# PDM_Mk21.net
KiCad netlist of a schematic drawn in Altium Designer
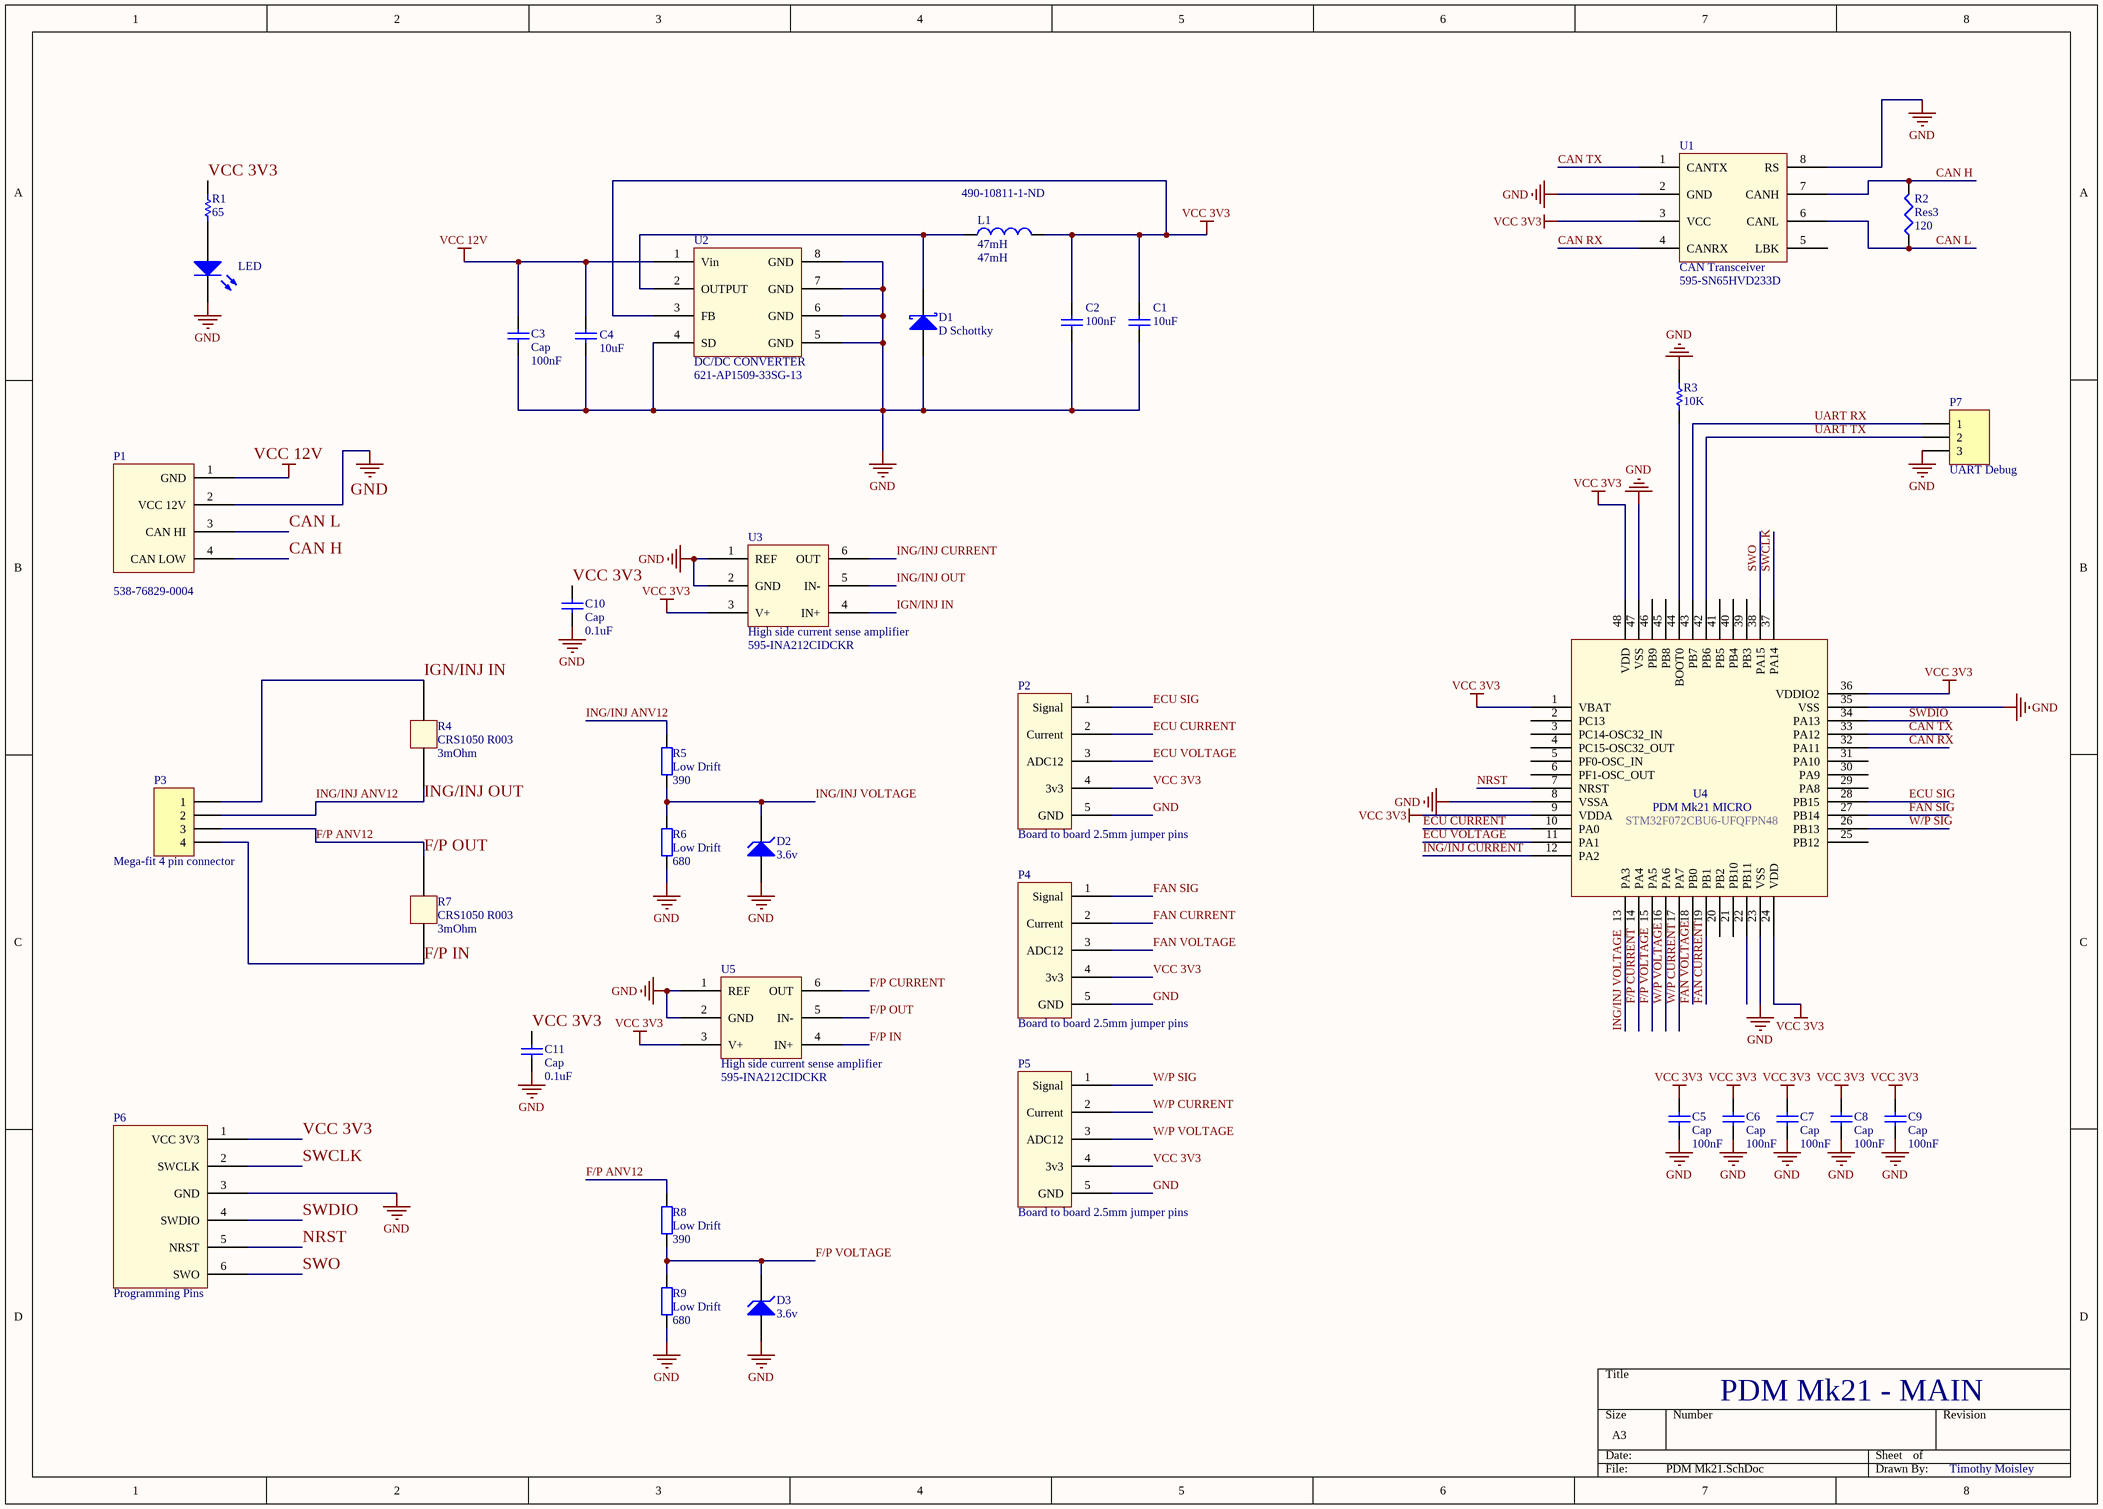
[diagram p0: PDM Mk21.SchDoc]

(export (version "E")
  (design (tool "Eeschema 10.0.6"))
  (components
    (comp (ref "C1")
      (value "10uF")
      (footprint "SMD CAPACITOR 220UF 16V")
      (description "Capacitor (Semiconductor SIM Model)")
      (fields (field (name "PUBLISHER") "Altium Limited"))
      (libsource (lib "Miscellaneous Devices") (part "Cap Semi"))
    )
    (comp (ref "C2")
      (value "100nF")
      (footprint "R0805")
      (description "Capacitor (Semiconductor SIM Model)")
      (fields (field (name "PUBLISHER") "Altium Limited"))
      (libsource (lib "Miscellaneous Devices") (part "Cap Semi"))
    )
    (comp (ref "C3")
      (value "Cap")
      (footprint "R0805")
      (description "Capacitor")
      (fields (field (name "ALTIUM_VALUE") "100nF") (field (name "PUBLISHER") "Altium Limited"))
      (libsource (lib "Miscellaneous Devices") (part "Cap"))
    )
    (comp (ref "C4")
      (value "10uF")
      (footprint "SMD CAPACITOR 220UF 16V")
      (description "Capacitor (Semiconductor SIM Model)")
      (fields (field (name "PUBLISHER") "Altium Limited"))
      (libsource (lib "Miscellaneous Devices") (part "Cap Semi"))
    )
    (comp (ref "C5")
      (value "Cap")
      (footprint "R0805")
      (description "Capacitor")
      (fields (field (name "ALTIUM_VALUE") "100nF") (field (name "PUBLISHER") "Altium Limited"))
      (libsource (lib "Miscellaneous Devices") (part "Cap"))
    )
    (comp (ref "C6")
      (value "Cap")
      (footprint "R0805")
      (description "Capacitor")
      (fields (field (name "ALTIUM_VALUE") "100nF") (field (name "PUBLISHER") "Altium Limited"))
      (libsource (lib "Miscellaneous Devices") (part "Cap"))
    )
    (comp (ref "C7")
      (value "Cap")
      (footprint "R0805")
      (description "Capacitor")
      (fields (field (name "ALTIUM_VALUE") "100nF") (field (name "PUBLISHER") "Altium Limited"))
      (libsource (lib "Miscellaneous Devices") (part "Cap"))
    )
    (comp (ref "C8")
      (value "Cap")
      (footprint "R0805")
      (description "Capacitor")
      (fields (field (name "ALTIUM_VALUE") "100nF") (field (name "PUBLISHER") "Altium Limited"))
      (libsource (lib "Miscellaneous Devices") (part "Cap"))
    )
    (comp (ref "C9")
      (value "Cap")
      (footprint "R0805")
      (description "Capacitor")
      (fields (field (name "ALTIUM_VALUE") "100nF") (field (name "PUBLISHER") "Altium Limited"))
      (libsource (lib "Miscellaneous Devices") (part "Cap"))
    )
    (comp (ref "C10")
      (value "Cap")
      (footprint "R0805")
      (description "Capacitor")
      (fields (field (name "ALTIUM_VALUE") "0.1uF") (field (name "PUBLISHER") "Altium Limited"))
      (libsource (lib "Miscellaneous Devices") (part "Cap"))
    )
    (comp (ref "C11")
      (value "Cap")
      (footprint "R0805")
      (description "Capacitor")
      (fields (field (name "ALTIUM_VALUE") "0.1uF") (field (name "PUBLISHER") "Altium Limited"))
      (libsource (lib "Miscellaneous Devices") (part "Cap"))
    )
    (comp (ref "D1")
      (value "D Schottky")
      (footprint "Diode")
      (description "Schottky Diode")
      (fields (field (name "PUBLISHER") "Altium Limited"))
      (libsource (lib "Miscellaneous Devices") (part "D Schottky"))
    )
    (comp (ref "D2")
      (value "3.6v")
      (footprint "BZX84CxxxET1G")
      (description "Zener Diode")
      (fields (field (name "PUBLISHER") "Altium Limited"))
      (libsource (lib "Miscellaneous Devices") (part "D Zener"))
    )
    (comp (ref "D3")
      (value "3.6v")
      (footprint "BZX84CxxxET1G")
      (description "Zener Diode")
      (fields (field (name "PUBLISHER") "Altium Limited"))
      (libsource (lib "Miscellaneous Devices") (part "D Zener"))
    )
    (comp (ref "L1")
      (value "47mH")
      (footprint "Inductor")
      (description "Inductor")
      (fields
        (field (name "ALTIUM_VALUE") "47mH")
        (field (name "MANUFACTURER") "Murata - TOKO")
        (field (name "MANUFACTURER PART NUMBER") "1255AY-470M=P3")
        (field (name "SUPPLIER PART NUMBER 2") "490-10811-1-ND")
        (field (name "PUBLISHER") "Altium Limited")
      )
      (libsource (lib "Miscellaneous Devices") (part "Inductor"))
    )
    (comp (ref "LED")
      (value "~")
      (footprint "LED-0")
      (description "Typical INFRARED GaAs LED")
      (fields (field (name "PUBLISHER") "Altium Limited"))
      (libsource (lib "Miscellaneous Devices") (part "LED0"))
    )
    (comp (ref "P1")
      (value "Mega-fit 4 pin connector")
      (footprint "SMD 4Wire")
      (description "MOLEX mega-fit 4 pin connector")
      (fields
        (field (name "MANUFACTURER") "MOLEX")
        (field (name "MANUFACTURER PART NO.") "76829-0004")
        (field (name "SUPPLIER PART NO.") "538-76829-0004")
      )
      (libsource (lib "PDM Mk21") (part "Mega-fit 4 pin connector"))
    )
    (comp (ref "P2")
      (value "Board to board 2.5mm jumper pins")
      (footprint "Board-Board Jumper")
      (libsource (lib "PDM Mk21") (part "Board-Board Jumper"))
    )
    (comp (ref "P3")
      (value "Mega-fit 4 pin connector")
      (footprint "Mega-fit 4 pin connector")
      (description "Header, 4-Pin")
      (fields (field (name "PUBLISHER") "Altium Limited"))
      (libsource (lib "Miscellaneous Connectors") (part "Header 4"))
    )
    (comp (ref "P4")
      (value "Board to board 2.5mm jumper pins")
      (footprint "Board-Board Jumper")
      (libsource (lib "PDM Mk21") (part "Board-Board Jumper"))
    )
    (comp (ref "P5")
      (value "Board to board 2.5mm jumper pins")
      (footprint "Board-Board Jumper")
      (libsource (lib "PDM Mk21") (part "Board-Board Jumper"))
    )
    (comp (ref "P6")
      (value "Programming Pins")
      (footprint "Programming Pins")
      (description "STM32 micro programming pins")
      (libsource (lib "PDM Mk21") (part "Programming Pins"))
    )
    (comp (ref "P7")
      (value "UART Debug")
      (footprint "HDR1X3")
      (description "Header, 3-Pin")
      (fields (field (name "PUBLISHER") "Altium Limited"))
      (libsource (lib "Miscellaneous Connectors") (part "Header 3"))
    )
    (comp (ref "R1")
      (value "65")
      (footprint "R0805")
      (description "Resistor")
      (fields (field (name "Comment") "GND") (field (name "PUBLISHER") "Altium Limited"))
      (libsource (lib "Miscellaneous Devices") (part "Res1"))
    )
    (comp (ref "R2")
      (value "Res3")
      (footprint "J1-0603")
      (description "Resistor")
      (fields (field (name "ALTIUM_VALUE") "120") (field (name "PUBLISHER") "Altium Limited"))
      (libsource (lib "Miscellaneous Devices") (part "Res3"))
    )
    (comp (ref "R3")
      (value "10K")
      (footprint "R0805")
      (description "Resistor")
      (fields (field (name "Comment") "GND") (field (name "PUBLISHER") "Altium Limited"))
      (libsource (lib "Miscellaneous Devices") (part "Res1"))
    )
    (comp (ref "R4")
      (value "CRS1050 R003")
      (footprint "CRS1050")
      (description "Current Shunt Resistor")
      (fields (field (name "ALTIUM_VALUE") "3mOhm"))
      (libsource (lib "PDM Mk21") (part "CSR1050"))
    )
    (comp (ref "R5")
      (value "Low Drift")
      (footprint "R0805")
      (description "Resistor")
      (fields (field (name "ALTIUM_VALUE") "390") (field (name "PUBLISHER") "Altium Limited"))
      (libsource (lib "Miscellaneous Devices") (part "Res2"))
    )
    (comp (ref "R6")
      (value "Low Drift")
      (footprint "R0805")
      (description "Resistor")
      (fields (field (name "ALTIUM_VALUE") "680") (field (name "PUBLISHER") "Altium Limited"))
      (libsource (lib "Miscellaneous Devices") (part "Res2"))
    )
    (comp (ref "R7")
      (value "CRS1050 R003")
      (footprint "CRS1050")
      (description "Current Shunt Resistor")
      (fields (field (name "ALTIUM_VALUE") "3mOhm"))
      (libsource (lib "") (part "CSR1050_1"))
    )
    (comp (ref "R8")
      (value "Low Drift")
      (footprint "R0805")
      (description "Resistor")
      (fields (field (name "ALTIUM_VALUE") "390") (field (name "PUBLISHER") "Altium Limited"))
      (libsource (lib "Miscellaneous Devices") (part "Res2"))
    )
    (comp (ref "R9")
      (value "Low Drift")
      (footprint "R0805")
      (description "Resistor")
      (fields (field (name "ALTIUM_VALUE") "680") (field (name "PUBLISHER") "Altium Limited"))
      (libsource (lib "Miscellaneous Devices") (part "Res2"))
    )
    (comp (ref "U1")
      (value "CAN Transceiver")
      (footprint "CAN Transceiver")
      (fields (field (name "SUPPLIER PART NO.") "595-SN65HVD233D"))
      (libsource (lib "PDM Mk21") (part "595-SN65HVD233D"))
    )
    (comp (ref "U2")
      (value "DC/DC CONVERTER")
      (footprint "DC/DC Converter")
      (fields (field (name "SUPPLIER PART NUMBER") "621-AP1509-33SG-13"))
      (libsource (lib "PDM Mk21") (part "AP1509-33SG-13"))
    )
    (comp (ref "U3")
      (value "High side current sense amplifier")
      (footprint "INA212")
      (fields
        (field (name "MANUFACTURER") "Texas Instruments")
        (field (name "MANUFACTURER PART NO.") "INA212CIDCKR")
        (field (name "SUPPLIER PART NUMBER") "595-INA212CIDCKR")
      )
      (libsource (lib "PDM Mk21") (part "INA212"))
    )
    (comp (ref "U4")
      (value "PDM Mk21 MICRO")
      (footprint "QFN50P700X700X60_HS-49N")
      (fields
        (field (name "MANUFACTURER") "ST Microelectrics")
        (field (name "PART NUMBER") "STM32F072CBU6-UFQFPN48")
      )
      (libsource (lib "PDM Mk21") (part "STM32F072CBU6"))
    )
    (comp (ref "U5")
      (value "High side current sense amplifier")
      (footprint "INA212")
      (fields
        (field (name "MANUFACTURER") "Texas Instruments")
        (field (name "MANUFACTURER PART NO.") "INA212CIDCKR")
        (field (name "SUPPLIER PART NUMBER") "595-INA212CIDCKR")
      )
      (libsource (lib "PDM Mk21") (part "INA212"))
    )
  )
  (nets
    (net (code "1") (name "/CAN H") (class "Default")
      (node (ref "P1") (pin "4") (pinfunction "CAN_LOW_4") (pintype "passive"))
      (node (ref "R2") (pin "2") (pinfunction "2_2") (pintype "passive"))
      (node (ref "U1") (pin "7") (pinfunction "CANH_7") (pintype "passive"))
    )
    (net (code "2") (name "/CAN L") (class "Default")
      (node (ref "P1") (pin "3") (pinfunction "CAN_HI_3") (pintype "passive"))
      (node (ref "R2") (pin "1") (pinfunction "1_1") (pintype "passive"))
      (node (ref "U1") (pin "6") (pinfunction "CANL_6") (pintype "passive"))
    )
    (net (code "3") (name "/CAN RX") (class "Default")
      (node (ref "U1") (pin "4") (pinfunction "CANRX_4") (pintype "passive"))
      (node (ref "U4") (pin "32") (pinfunction "PA11_32") (pintype "passive"))
    )
    (net (code "4") (name "/CAN TX") (class "Default")
      (node (ref "U1") (pin "1") (pinfunction "CANTX_1") (pintype "passive"))
      (node (ref "U4") (pin "33") (pinfunction "PA12_33") (pintype "passive"))
    )
    (net (code "5") (name "/ECU CURRENT") (class "Default")
      (node (ref "P2") (pin "2") (pinfunction "Current_2") (pintype "passive"))
      (node (ref "U4") (pin "10") (pinfunction "PA0_10") (pintype "passive"))
    )
    (net (code "6") (name "/ECU SIG") (class "Default")
      (node (ref "P2") (pin "1") (pinfunction "Signal_1") (pintype "passive"))
      (node (ref "U4") (pin "28") (pinfunction "PB15_28") (pintype "passive"))
    )
    (net (code "7") (name "/ECU VOLTAGE") (class "Default")
      (node (ref "P2") (pin "3") (pinfunction "ADC12_3") (pintype "passive"))
      (node (ref "U4") (pin "11") (pinfunction "PA1_11") (pintype "passive"))
    )
    (net (code "8") (name "/FAN CURRENT") (class "Default")
      (node (ref "P4") (pin "2") (pinfunction "Current_2") (pintype "passive"))
      (node (ref "U4") (pin "19") (pinfunction "PB1_19") (pintype "passive"))
    )
    (net (code "9") (name "/FAN SIG") (class "Default")
      (node (ref "P4") (pin "1") (pinfunction "Signal_1") (pintype "passive"))
      (node (ref "U4") (pin "27") (pinfunction "PB14_27") (pintype "passive"))
    )
    (net (code "10") (name "/FAN VOLTAGE") (class "Default")
      (node (ref "P4") (pin "3") (pinfunction "ADC12_3") (pintype "passive"))
      (node (ref "U4") (pin "18") (pinfunction "PB0_18") (pintype "passive"))
    )
    (net (code "11") (name "/F{slash}P ANV12") (class "Default")
      (node (ref "P3") (pin "3") (pinfunction "3_3") (pintype "passive"))
      (node (ref "R7") (pin "2") (pinfunction "2_2") (pintype "passive"))
      (node (ref "R8") (pin "2") (pinfunction "2_2") (pintype "passive"))
      (node (ref "U5") (pin "5") (pinfunction "IN-_5") (pintype "passive"))
    )
    (net (code "12") (name "/F{slash}P CURRENT") (class "Default")
      (node (ref "U4") (pin "14") (pinfunction "PA4_14") (pintype "passive"))
      (node (ref "U5") (pin "6") (pinfunction "OUT_6") (pintype "passive"))
    )
    (net (code "13") (name "/F{slash}P IN") (class "Default")
      (node (ref "P3") (pin "4") (pinfunction "4_4") (pintype "passive"))
      (node (ref "R7") (pin "1") (pinfunction "1_1") (pintype "passive"))
      (node (ref "U5") (pin "4") (pinfunction "IN+_4") (pintype "passive"))
    )
    (net (code "14") (name "/F{slash}P VOLTAGE") (class "Default")
      (node (ref "D3") (pin "2") (pinfunction "K_2") (pintype "passive"))
      (node (ref "R8") (pin "1") (pinfunction "1_1") (pintype "passive"))
      (node (ref "R9") (pin "2") (pinfunction "2_2") (pintype "passive"))
      (node (ref "U4") (pin "15") (pinfunction "PA5_15") (pintype "passive"))
    )
    (net (code "15") (name "/IGN{slash}INJ IN") (class "Default")
      (node (ref "P3") (pin "1") (pinfunction "1_1") (pintype "passive"))
      (node (ref "R4") (pin "1") (pinfunction "1_1") (pintype "passive"))
      (node (ref "U3") (pin "4") (pinfunction "IN+_4") (pintype "passive"))
    )
    (net (code "16") (name "/ING{slash}INJ ANV12") (class "Default")
      (node (ref "P3") (pin "2") (pinfunction "2_2") (pintype "passive"))
      (node (ref "R4") (pin "2") (pinfunction "2_2") (pintype "passive"))
      (node (ref "R5") (pin "2") (pinfunction "2_2") (pintype "passive"))
      (node (ref "U3") (pin "5") (pinfunction "IN-_5") (pintype "passive"))
    )
    (net (code "17") (name "/ING{slash}INJ CURRENT") (class "Default")
      (node (ref "U3") (pin "6") (pinfunction "OUT_6") (pintype "passive"))
      (node (ref "U4") (pin "12") (pinfunction "PA2_12") (pintype "passive"))
    )
    (net (code "18") (name "/ING{slash}INJ VOLTAGE") (class "Default")
      (node (ref "D2") (pin "2") (pinfunction "K_2") (pintype "passive"))
      (node (ref "R5") (pin "1") (pinfunction "1_1") (pintype "passive"))
      (node (ref "R6") (pin "2") (pinfunction "2_2") (pintype "passive"))
      (node (ref "U4") (pin "13") (pinfunction "PA3_13") (pintype "passive"))
    )
    (net (code "19") (name "/NRST") (class "Default")
      (node (ref "P6") (pin "5") (pinfunction "NRST_5") (pintype "passive"))
      (node (ref "U4") (pin "7") (pinfunction "NRST_7") (pintype "passive"))
    )
    (net (code "20") (name "/SWCLK") (class "Default")
      (node (ref "P6") (pin "2") (pinfunction "SWCLK_2") (pintype "passive"))
      (node (ref "U4") (pin "37") (pinfunction "PA14_37") (pintype "passive"))
    )
    (net (code "21") (name "/SWDIO") (class "Default")
      (node (ref "P6") (pin "4") (pinfunction "SWDIO_4") (pintype "passive"))
      (node (ref "U4") (pin "34") (pinfunction "PA13_34") (pintype "passive"))
    )
    (net (code "22") (name "/SWO") (class "Default")
      (node (ref "P6") (pin "6") (pinfunction "SWO_6") (pintype "passive"))
      (node (ref "U4") (pin "38") (pinfunction "PA15_38") (pintype "passive"))
    )
    (net (code "23") (name "/UART RX") (class "Default")
      (node (ref "P7") (pin "1") (pinfunction "1_1") (pintype "passive"))
      (node (ref "U4") (pin "43") (pinfunction "PB7_43") (pintype "passive"))
    )
    (net (code "24") (name "/UART TX") (class "Default")
      (node (ref "P7") (pin "2") (pinfunction "2_2") (pintype "passive"))
      (node (ref "U4") (pin "42") (pinfunction "PB6_42") (pintype "passive"))
    )
    (net (code "25") (name "/W{slash}P CURRENT") (class "Default")
      (node (ref "P5") (pin "2") (pinfunction "Current_2") (pintype "passive"))
      (node (ref "U4") (pin "17") (pinfunction "PA7_17") (pintype "passive"))
    )
    (net (code "26") (name "/W{slash}P SIG") (class "Default")
      (node (ref "P5") (pin "1") (pinfunction "Signal_1") (pintype "passive"))
      (node (ref "U4") (pin "26") (pinfunction "PB13_26") (pintype "passive"))
    )
    (net (code "27") (name "/W{slash}P VOLTAGE") (class "Default")
      (node (ref "P5") (pin "3") (pinfunction "ADC12_3") (pintype "passive"))
      (node (ref "U4") (pin "16") (pinfunction "PA6_16") (pintype "passive"))
    )
    (net (code "28") (name "GND") (class "Default")
      (node (ref "C1") (pin "1") (pinfunction "1_1") (pintype "passive"))
      (node (ref "C10") (pin "1") (pinfunction "1_1") (pintype "passive"))
      (node (ref "C11") (pin "1") (pinfunction "1_1") (pintype "passive"))
      (node (ref "C2") (pin "1") (pinfunction "1_1") (pintype "passive"))
      (node (ref "C3") (pin "2") (pinfunction "2_2") (pintype "passive"))
      (node (ref "C4") (pin "2") (pinfunction "2_2") (pintype "passive"))
      (node (ref "C5") (pin "1") (pinfunction "1_1") (pintype "passive"))
      (node (ref "C6") (pin "1") (pinfunction "1_1") (pintype "passive"))
      (node (ref "C7") (pin "1") (pinfunction "1_1") (pintype "passive"))
      (node (ref "C8") (pin "1") (pinfunction "1_1") (pintype "passive"))
      (node (ref "C9") (pin "1") (pinfunction "1_1") (pintype "passive"))
      (node (ref "D1") (pin "1") (pinfunction "A_1") (pintype "passive"))
      (node (ref "D2") (pin "1") (pinfunction "A_1") (pintype "passive"))
      (node (ref "D3") (pin "1") (pinfunction "A_1") (pintype "passive"))
      (node (ref "LED") (pin "2") (pinfunction "K_2") (pintype "passive"))
      (node (ref "P1") (pin "2") (pinfunction "VCC_12V_2") (pintype "passive"))
      (node (ref "P2") (pin "5") (pinfunction "GND_5") (pintype "passive"))
      (node (ref "P4") (pin "5") (pinfunction "GND_5") (pintype "passive"))
      (node (ref "P5") (pin "5") (pinfunction "GND_5") (pintype "passive"))
      (node (ref "P6") (pin "3") (pinfunction "GND_3") (pintype "passive"))
      (node (ref "P7") (pin "3") (pinfunction "3_3") (pintype "passive"))
      (node (ref "R3") (pin "2") (pinfunction "2_2") (pintype "passive"))
      (node (ref "R6") (pin "1") (pinfunction "1_1") (pintype "passive"))
      (node (ref "R9") (pin "1") (pinfunction "1_1") (pintype "passive"))
      (node (ref "U1") (pin "2") (pinfunction "GND_2") (pintype "passive"))
      (node (ref "U1") (pin "8") (pinfunction "RS_8") (pintype "passive"))
      (node (ref "U2") (pin "4") (pinfunction "SD_4") (pintype "passive"))
      (node (ref "U2") (pin "5") (pinfunction "GND_5") (pintype "passive"))
      (node (ref "U2") (pin "6") (pinfunction "GND_6") (pintype "passive"))
      (node (ref "U2") (pin "7") (pinfunction "GND_7") (pintype "passive"))
      (node (ref "U2") (pin "8") (pinfunction "GND_8") (pintype "passive"))
      (node (ref "U3") (pin "1") (pinfunction "REF_1") (pintype "passive"))
      (node (ref "U3") (pin "2") (pinfunction "GND_2") (pintype "passive"))
      (node (ref "U4") (pin "23") (pinfunction "VSS_23") (pintype "passive"))
      (node (ref "U4") (pin "35") (pinfunction "VSS_35") (pintype "passive"))
      (node (ref "U4") (pin "47") (pinfunction "VSS_47") (pintype "passive"))
      (node (ref "U4") (pin "8") (pinfunction "VSSA_8") (pintype "passive"))
      (node (ref "U5") (pin "1") (pinfunction "REF_1") (pintype "passive"))
      (node (ref "U5") (pin "2") (pinfunction "GND_2") (pintype "passive"))
    )
    (net (code "29") (name "Net-(D1-K)") (class "Default")
      (node (ref "D1") (pin "2") (pinfunction "K_2") (pintype "passive"))
      (node (ref "L1") (pin "1") (pinfunction "1_1") (pintype "passive"))
      (node (ref "U2") (pin "2") (pinfunction "OUTPUT_2") (pintype "passive"))
    )
    (net (code "30") (name "Net-(LED-A)") (class "Default")
      (node (ref "LED") (pin "1") (pinfunction "A_1") (pintype "passive"))
      (node (ref "R1") (pin "2") (pinfunction "2_2") (pintype "passive"))
    )
    (net (code "31") (name "Net-(U4-BOOT0)") (class "Default")
      (node (ref "R3") (pin "1") (pinfunction "1_1") (pintype "passive"))
      (node (ref "U4") (pin "44") (pinfunction "BOOT0_44") (pintype "passive"))
    )
    (net (code "32") (name "VCC 3V3") (class "Default")
      (node (ref "C1") (pin "2") (pinfunction "2_2") (pintype "passive"))
      (node (ref "C10") (pin "2") (pinfunction "2_2") (pintype "passive"))
      (node (ref "C11") (pin "2") (pinfunction "2_2") (pintype "passive"))
      (node (ref "C2") (pin "2") (pinfunction "2_2") (pintype "passive"))
      (node (ref "C5") (pin "2") (pinfunction "2_2") (pintype "passive"))
      (node (ref "C6") (pin "2") (pinfunction "2_2") (pintype "passive"))
      (node (ref "C7") (pin "2") (pinfunction "2_2") (pintype "passive"))
      (node (ref "C8") (pin "2") (pinfunction "2_2") (pintype "passive"))
      (node (ref "C9") (pin "2") (pinfunction "2_2") (pintype "passive"))
      (node (ref "L1") (pin "2") (pinfunction "2_2") (pintype "passive"))
      (node (ref "P2") (pin "4") (pinfunction "3v3_4") (pintype "passive"))
      (node (ref "P4") (pin "4") (pinfunction "3v3_4") (pintype "passive"))
      (node (ref "P5") (pin "4") (pinfunction "3v3_4") (pintype "passive"))
      (node (ref "P6") (pin "1") (pinfunction "VCC_3V3_1") (pintype "passive"))
      (node (ref "R1") (pin "1") (pinfunction "1_1") (pintype "passive"))
      (node (ref "U1") (pin "3") (pinfunction "VCC_3") (pintype "passive"))
      (node (ref "U2") (pin "3") (pinfunction "FB_3") (pintype "passive"))
      (node (ref "U3") (pin "3") (pinfunction "V+_3") (pintype "passive"))
      (node (ref "U4") (pin "1") (pinfunction "VBAT_1") (pintype "passive"))
      (node (ref "U4") (pin "24") (pinfunction "VDD_24") (pintype "passive"))
      (node (ref "U4") (pin "36") (pinfunction "VDDIO2_36") (pintype "passive"))
      (node (ref "U4") (pin "48") (pinfunction "VDD_48") (pintype "passive"))
      (node (ref "U4") (pin "9") (pinfunction "VDDA_9") (pintype "passive"))
      (node (ref "U5") (pin "3") (pinfunction "V+_3") (pintype "passive"))
    )
    (net (code "33") (name "VCC 12V") (class "Default")
      (node (ref "C3") (pin "1") (pinfunction "1_1") (pintype "passive"))
      (node (ref "C4") (pin "1") (pinfunction "1_1") (pintype "passive"))
      (node (ref "P1") (pin "1") (pinfunction "GND_1") (pintype "passive"))
      (node (ref "U2") (pin "1") (pinfunction "Vin_1") (pintype "passive"))
    )
    (net (code "34") (name "unconnected-(U1-LBK-Pad5)") (class "Default")
      (node (ref "U1") (pin "5") (pinfunction "LBK_5") (pintype "passive"))
    )
    (net (code "35") (name "unconnected-(U4-PA8-Pad29)") (class "Default")
      (node (ref "U4") (pin "29") (pinfunction "PA8_29") (pintype "passive"))
    )
    (net (code "36") (name "unconnected-(U4-PA9-Pad30)") (class "Default")
      (node (ref "U4") (pin "30") (pinfunction "PA9_30") (pintype "passive"))
    )
    (net (code "37") (name "unconnected-(U4-PA10-Pad31)") (class "Default")
      (node (ref "U4") (pin "31") (pinfunction "PA10_31") (pintype "passive"))
    )
    (net (code "38") (name "unconnected-(U4-PB2-Pad20)") (class "Default")
      (node (ref "U4") (pin "20") (pinfunction "PB2_20") (pintype "passive"))
    )
    (net (code "39") (name "unconnected-(U4-PB3-Pad39)") (class "Default")
      (node (ref "U4") (pin "39") (pinfunction "PB3_39") (pintype "passive"))
    )
    (net (code "40") (name "unconnected-(U4-PB4-Pad40)") (class "Default")
      (node (ref "U4") (pin "40") (pinfunction "PB4_40") (pintype "passive"))
    )
    (net (code "41") (name "unconnected-(U4-PB5-Pad41)") (class "Default")
      (node (ref "U4") (pin "41") (pinfunction "PB5_41") (pintype "passive"))
    )
    (net (code "42") (name "unconnected-(U4-PB8-Pad45)") (class "Default")
      (node (ref "U4") (pin "45") (pinfunction "PB8_45") (pintype "passive"))
    )
    (net (code "43") (name "unconnected-(U4-PB9-Pad46)") (class "Default")
      (node (ref "U4") (pin "46") (pinfunction "PB9_46") (pintype "passive"))
    )
    (net (code "44") (name "unconnected-(U4-PB10-Pad21)") (class "Default")
      (node (ref "U4") (pin "21") (pinfunction "PB10_21") (pintype "passive"))
    )
    (net (code "45") (name "unconnected-(U4-PB11-Pad22)") (class "Default")
      (node (ref "U4") (pin "22") (pinfunction "PB11_22") (pintype "passive"))
    )
    (net (code "46") (name "unconnected-(U4-PB12-Pad25)") (class "Default")
      (node (ref "U4") (pin "25") (pinfunction "PB12_25") (pintype "passive"))
    )
    (net (code "47") (name "unconnected-(U4-PC13-Pad2)") (class "Default")
      (node (ref "U4") (pin "2") (pinfunction "PC13_2") (pintype "passive"))
    )
    (net (code "48") (name "unconnected-(U4-PC14-OSC32_IN-Pad3)") (class "Default")
      (node (ref "U4") (pin "3") (pinfunction "PC14-OSC32_IN_3") (pintype "passive"))
    )
    (net (code "49") (name "unconnected-(U4-PC15-OSC32_OUT-Pad4)") (class "Default")
      (node (ref "U4") (pin "4") (pinfunction "PC15-OSC32_OUT_4") (pintype "passive"))
    )
    (net (code "50") (name "unconnected-(U4-PF0-OSC_IN-Pad5)") (class "Default")
      (node (ref "U4") (pin "5") (pinfunction "PF0-OSC_IN_5") (pintype "passive"))
    )
    (net (code "51") (name "unconnected-(U4-PF1-OSC_OUT-Pad6)") (class "Default")
      (node (ref "U4") (pin "6") (pinfunction "PF1-OSC_OUT_6") (pintype "passive"))
    )
  )
)
